# PCB-TOP.net
KiCad netlist of a schematic drawn in EAGLE
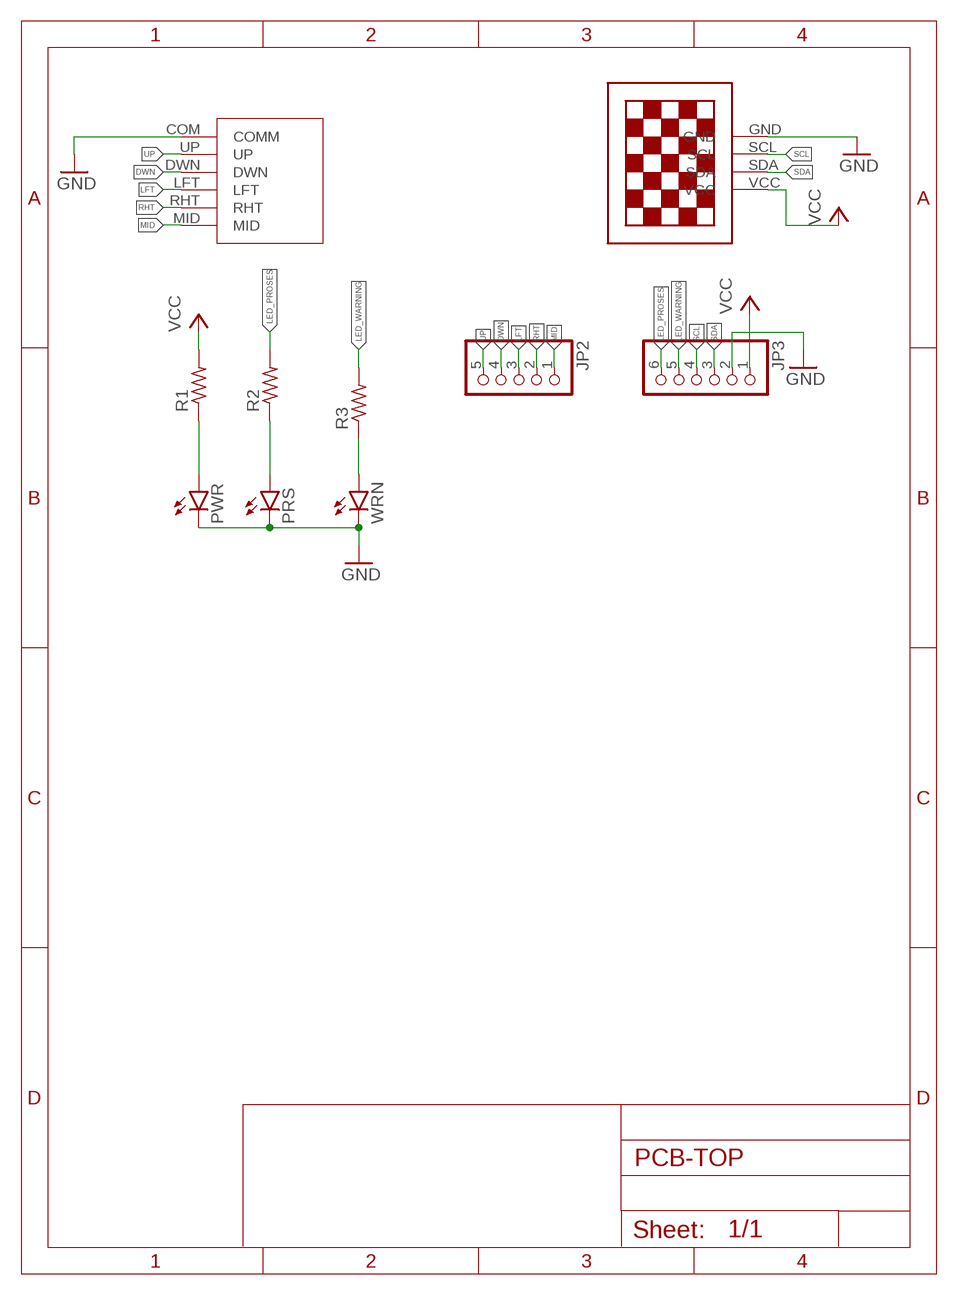
[diagram p0: schematic, sheet 1]

(export (version "E")
  (design (tool "Eeschema 10.0.6"))
  (components
    (comp (ref "JP2")
      (value "PINHD-1X5")
      (footprint "eagle-import:1X05")
      (libsource (lib "eagle-import") (part "PINHD-1X5"))
    )
    (comp (ref "JP3")
      (value "PINHD-1X6")
      (footprint "eagle-import:1X06")
      (libsource (lib "eagle-import") (part "PINHD-1X6"))
    )
    (comp (ref "NAV-SWITCH6P1")
      (value "NAV-SWITCH6P")
      (footprint "eagle-import:NAV-SWITCH6P")
      (libsource (lib "eagle-import") (part "NAV-SWITCH6P"))
    )
    (comp (ref "PRS")
      (value "TLLR4400")
      (footprint "eagle-import:LED3MM")
      (fields (field (name "MF") "VISHAY SEMICONDUCTOR"))
      (libsource (lib "eagle-import") (part "TLLR4400"))
    )
    (comp (ref "PWR")
      (value "TLLR4400")
      (footprint "eagle-import:LED3MM")
      (fields (field (name "MF") "VISHAY SEMICONDUCTOR"))
      (libsource (lib "eagle-import") (part "TLLR4400"))
    )
    (comp (ref "R1")
      (value "R-US_M0805")
      (footprint "eagle-import:M0805")
      (libsource (lib "eagle-import") (part "R-US_M0805"))
    )
    (comp (ref "R2")
      (value "R-US_M0805")
      (footprint "eagle-import:M0805")
      (libsource (lib "eagle-import") (part "R-US_M0805"))
    )
    (comp (ref "R3")
      (value "R-US_M0805")
      (footprint "eagle-import:M0805")
      (libsource (lib "eagle-import") (part "R-US_M0805"))
    )
    (comp (ref "U$1")
      (value "13\"OLED13\"OLED")
      (footprint "eagle-import:1.3_OLED")
      (libsource (lib "eagle-import") (part "13{dblquote}OLED13{dblquote}OLED"))
    )
    (comp (ref "WRN")
      (value "TLLR4400")
      (footprint "eagle-import:LED3MM")
      (fields (field (name "MF") "VISHAY SEMICONDUCTOR"))
      (libsource (lib "eagle-import") (part "TLLR4400"))
    )
  )
  (nets
    (net (code "1") (name "DWN") (class "Default")
      (node (ref "JP2") (pin "4") (pinfunction "4_4") (pintype "passive"))
      (node (ref "NAV-SWITCH6P1") (pin "DWN") (pinfunction "DWN_DWN") (pintype "bidirectional"))
    )
    (net (code "2") (name "GND") (class "Default")
      (node (ref "JP3") (pin "2") (pinfunction "2_2") (pintype "passive"))
      (node (ref "NAV-SWITCH6P1") (pin "COM") (pinfunction "COMM_COM") (pintype "bidirectional"))
      (node (ref "PRS") (pin "K") (pinfunction "C_K") (pintype "passive"))
      (node (ref "PWR") (pin "K") (pinfunction "C_K") (pintype "passive"))
      (node (ref "U$1") (pin "GND") (pinfunction "GND_GND") (pintype "bidirectional"))
      (node (ref "WRN") (pin "K") (pinfunction "C_K") (pintype "passive"))
    )
    (net (code "3") (name "LED_PROSES") (class "Default")
      (node (ref "JP3") (pin "6") (pinfunction "6_6") (pintype "passive"))
      (node (ref "R2") (pin "2") (pinfunction "2_2") (pintype "passive"))
    )
    (net (code "4") (name "LED_WARNING") (class "Default")
      (node (ref "JP3") (pin "5") (pinfunction "5_5") (pintype "passive"))
      (node (ref "R3") (pin "2") (pinfunction "2_2") (pintype "passive"))
    )
    (net (code "5") (name "LFT") (class "Default")
      (node (ref "JP2") (pin "3") (pinfunction "3_3") (pintype "passive"))
      (node (ref "NAV-SWITCH6P1") (pin "LFT") (pinfunction "LFT_LFT") (pintype "bidirectional"))
    )
    (net (code "6") (name "MID") (class "Default")
      (node (ref "JP2") (pin "1") (pinfunction "1_1") (pintype "passive"))
      (node (ref "NAV-SWITCH6P1") (pin "MID") (pinfunction "MID_MID") (pintype "bidirectional"))
    )
    (net (code "7") (name "Net-(PRS-PadA)") (class "Default")
      (node (ref "PRS") (pin "A") (pinfunction "A_A") (pintype "passive"))
      (node (ref "R2") (pin "1") (pinfunction "1_1") (pintype "passive"))
    )
    (net (code "8") (name "Net-(PWR-PadA)") (class "Default")
      (node (ref "PWR") (pin "A") (pinfunction "A_A") (pintype "passive"))
      (node (ref "R1") (pin "1") (pinfunction "1_1") (pintype "passive"))
    )
    (net (code "9") (name "Net-(R3-Pad1)") (class "Default")
      (node (ref "R3") (pin "1") (pinfunction "1_1") (pintype "passive"))
      (node (ref "WRN") (pin "A") (pinfunction "A_A") (pintype "passive"))
    )
    (net (code "10") (name "RHT") (class "Default")
      (node (ref "JP2") (pin "2") (pinfunction "2_2") (pintype "passive"))
      (node (ref "NAV-SWITCH6P1") (pin "RHT") (pinfunction "RHT_RHT") (pintype "bidirectional"))
    )
    (net (code "11") (name "SCL") (class "Default")
      (node (ref "JP3") (pin "4") (pinfunction "4_4") (pintype "passive"))
      (node (ref "U$1") (pin "SCL") (pinfunction "SCL_SCL") (pintype "bidirectional"))
    )
    (net (code "12") (name "SDA") (class "Default")
      (node (ref "JP3") (pin "3") (pinfunction "3_3") (pintype "passive"))
      (node (ref "U$1") (pin "SDA") (pinfunction "SDA_SDA") (pintype "bidirectional"))
    )
    (net (code "13") (name "UP") (class "Default")
      (node (ref "JP2") (pin "5") (pinfunction "5_5") (pintype "passive"))
      (node (ref "NAV-SWITCH6P1") (pin "UP") (pinfunction "UP_UP") (pintype "bidirectional"))
    )
    (net (code "14") (name "VCC") (class "Default")
      (node (ref "JP3") (pin "1") (pinfunction "1_1") (pintype "passive"))
      (node (ref "R1") (pin "2") (pinfunction "2_2") (pintype "passive"))
      (node (ref "U$1") (pin "VCC") (pinfunction "VCC_VCC") (pintype "bidirectional"))
    )
  )
)
